# pci-e_x1-breakout.net
KiCad netlist of a schematic drawn in EAGLE
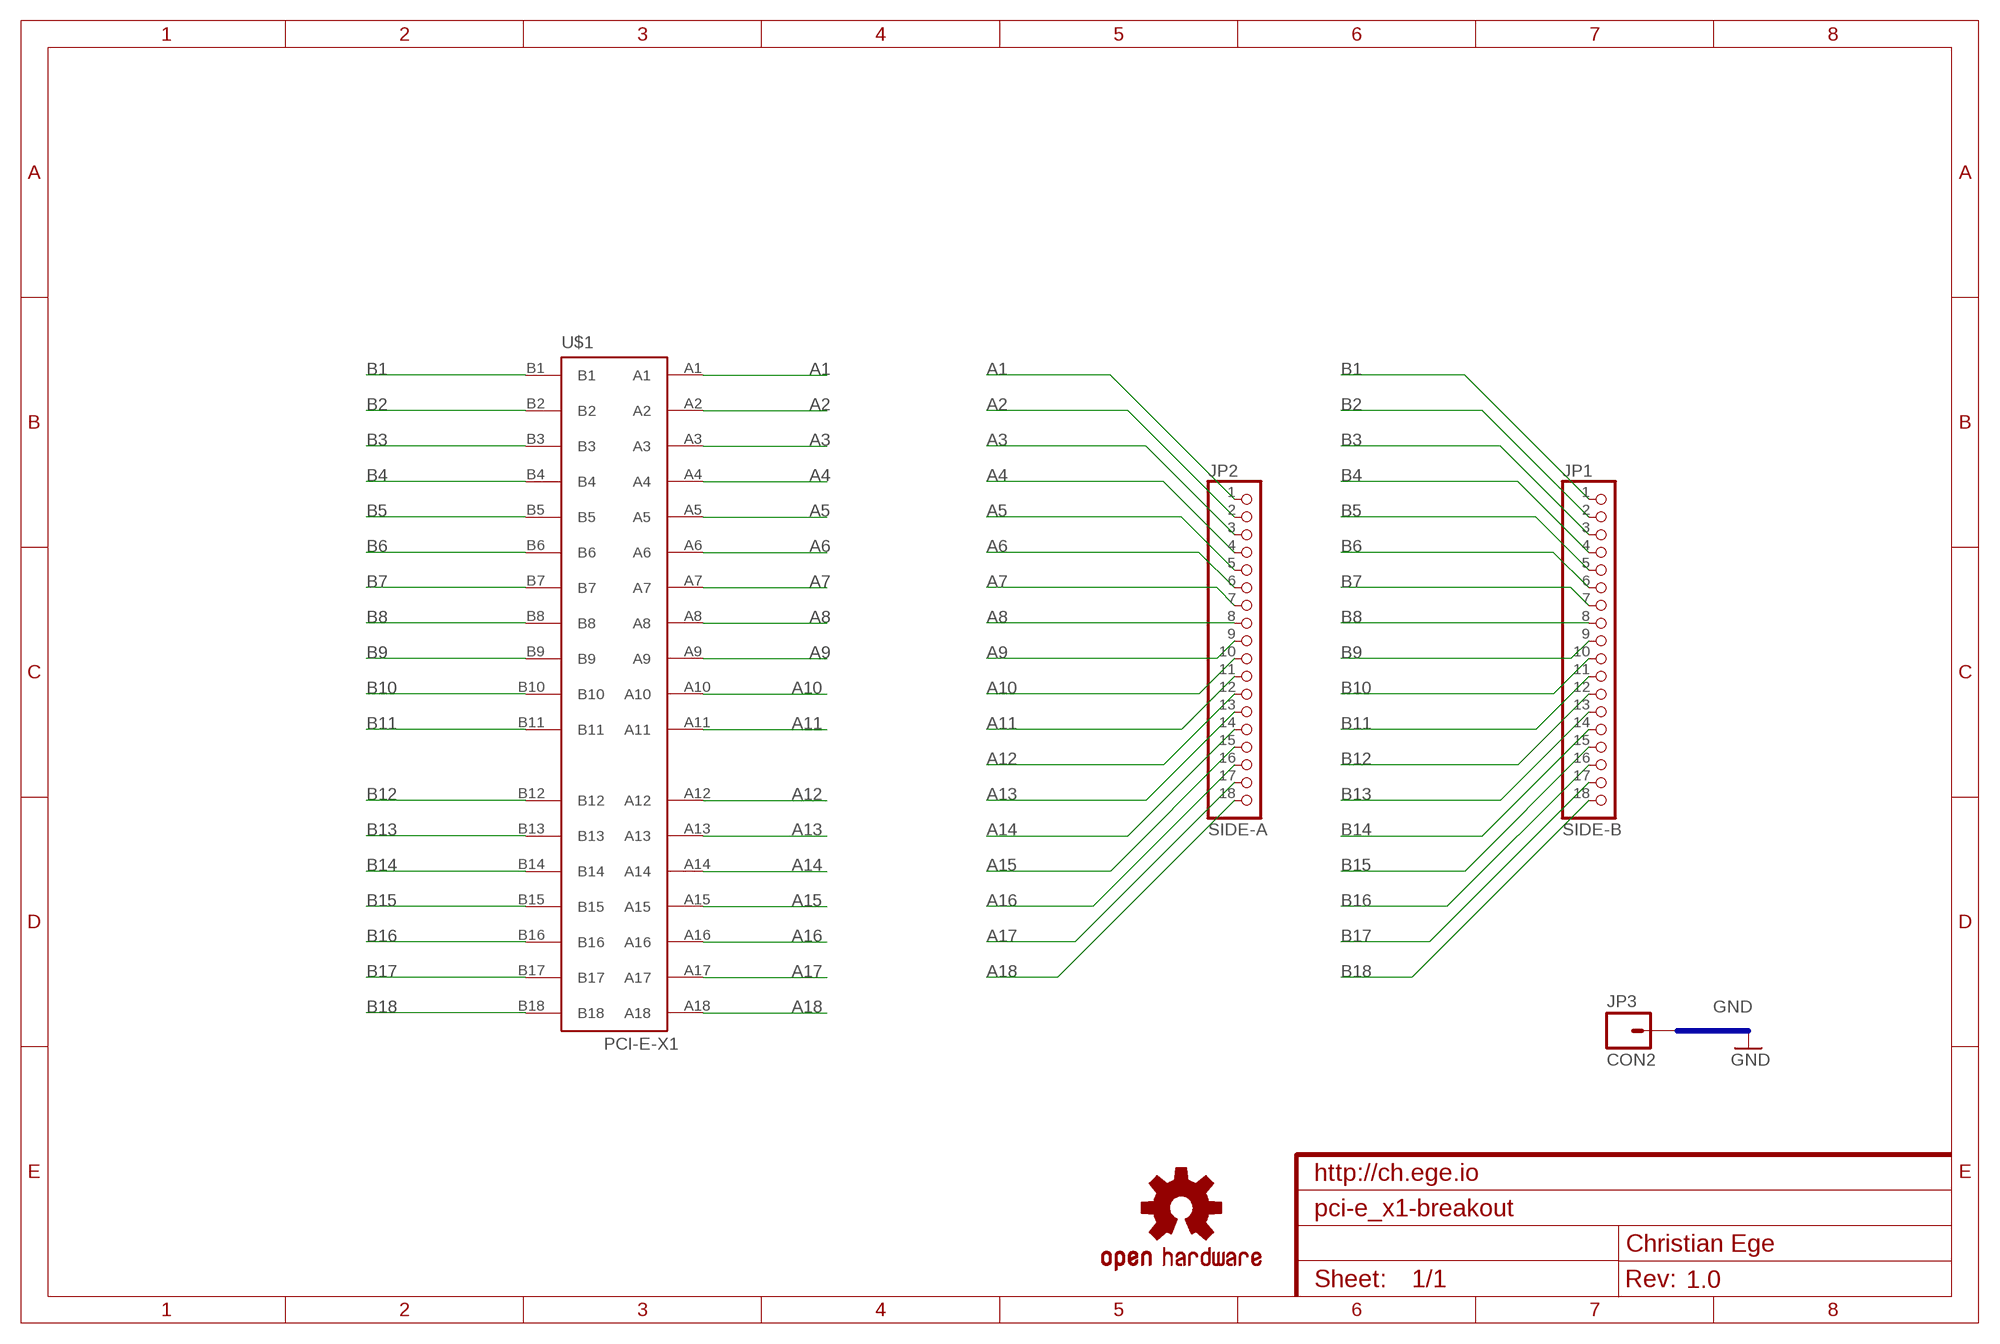
[diagram p0: schematic, sheet 1]

(export (version "E")
  (design (tool "Eeschema 10.0.6"))
  (components
    (comp (ref "JP1")
      (value "SIDE-B")
      (footprint "eagle-import:1X18")
      (libsource (lib "eagle-import") (part "PINHD-1X18"))
    )
    (comp (ref "JP2")
      (value "SIDE-A")
      (footprint "eagle-import:1X18")
      (libsource (lib "eagle-import") (part "PINHD-1X18"))
    )
    (comp (ref "JP3")
      (value "CON2")
      (footprint "eagle-import:1X01")
      (libsource (lib "eagle-import") (part "M01PTH"))
    )
    (comp (ref "LOGO1")
      (value "OSHW-LOGOS")
      (footprint "eagle-import:OSHW-LOGO-S")
      (libsource (lib "eagle-import") (part "OSHW-LOGOS"))
    )
    (comp (ref "U$1")
      (value "PCI-E-X1")
      (footprint "eagle-import:PCI-E-X1")
      (libsource (lib "eagle-import") (part "PCI-E-X1"))
    )
  )
  (nets
    (net (code "1") (name "/A1") (class "Default")
      (node (ref "JP2") (pin "1") (pinfunction "1_1") (pintype "passive"))
      (node (ref "U$1") (pin "A1") (pinfunction "A1_A1") (pintype "bidirectional"))
    )
    (net (code "2") (name "/A2") (class "Default")
      (node (ref "JP2") (pin "2") (pinfunction "2_2") (pintype "passive"))
      (node (ref "U$1") (pin "A2") (pinfunction "A2_A2") (pintype "bidirectional"))
    )
    (net (code "3") (name "/A3") (class "Default")
      (node (ref "JP2") (pin "3") (pinfunction "3_3") (pintype "passive"))
      (node (ref "U$1") (pin "A3") (pinfunction "A3_A3") (pintype "bidirectional"))
    )
    (net (code "4") (name "/A4") (class "Default")
      (node (ref "JP2") (pin "4") (pinfunction "4_4") (pintype "passive"))
      (node (ref "U$1") (pin "A4") (pinfunction "A4_A4") (pintype "bidirectional"))
    )
    (net (code "5") (name "/A5") (class "Default")
      (node (ref "JP2") (pin "5") (pinfunction "5_5") (pintype "passive"))
      (node (ref "U$1") (pin "A5") (pinfunction "A5_A5") (pintype "bidirectional"))
    )
    (net (code "6") (name "/A6") (class "Default")
      (node (ref "JP2") (pin "6") (pinfunction "6_6") (pintype "passive"))
      (node (ref "U$1") (pin "A6") (pinfunction "A6_A6") (pintype "bidirectional"))
    )
    (net (code "7") (name "/A7") (class "Default")
      (node (ref "JP2") (pin "7") (pinfunction "7_7") (pintype "passive"))
      (node (ref "U$1") (pin "A7") (pinfunction "A7_A7") (pintype "bidirectional"))
    )
    (net (code "8") (name "/A8") (class "Default")
      (node (ref "JP2") (pin "8") (pinfunction "8_8") (pintype "passive"))
      (node (ref "U$1") (pin "A8") (pinfunction "A8_A8") (pintype "bidirectional"))
    )
    (net (code "9") (name "/A9") (class "Default")
      (node (ref "JP2") (pin "9") (pinfunction "9_9") (pintype "passive"))
      (node (ref "U$1") (pin "A9") (pinfunction "A9_A9") (pintype "bidirectional"))
    )
    (net (code "10") (name "/A10") (class "Default")
      (node (ref "JP2") (pin "10") (pinfunction "10_10") (pintype "passive"))
      (node (ref "U$1") (pin "A10") (pinfunction "A10_A10") (pintype "bidirectional"))
    )
    (net (code "11") (name "/A11") (class "Default")
      (node (ref "JP2") (pin "11") (pinfunction "11_11") (pintype "passive"))
      (node (ref "U$1") (pin "A11") (pinfunction "A11_A11") (pintype "bidirectional"))
    )
    (net (code "12") (name "/A12") (class "Default")
      (node (ref "JP2") (pin "12") (pinfunction "12_12") (pintype "passive"))
      (node (ref "U$1") (pin "A12") (pinfunction "A12_A12") (pintype "bidirectional"))
    )
    (net (code "13") (name "/A13") (class "Default")
      (node (ref "JP2") (pin "13") (pinfunction "13_13") (pintype "passive"))
      (node (ref "U$1") (pin "A13") (pinfunction "A13_A13") (pintype "bidirectional"))
    )
    (net (code "14") (name "/A14") (class "Default")
      (node (ref "JP2") (pin "14") (pinfunction "14_14") (pintype "passive"))
      (node (ref "U$1") (pin "A14") (pinfunction "A14_A14") (pintype "bidirectional"))
    )
    (net (code "15") (name "/A15") (class "Default")
      (node (ref "JP2") (pin "15") (pinfunction "15_15") (pintype "passive"))
      (node (ref "U$1") (pin "A15") (pinfunction "A15_A15") (pintype "bidirectional"))
    )
    (net (code "16") (name "/A16") (class "Default")
      (node (ref "JP2") (pin "16") (pinfunction "16_16") (pintype "passive"))
      (node (ref "U$1") (pin "A16") (pinfunction "A16_A16") (pintype "bidirectional"))
    )
    (net (code "17") (name "/A17") (class "Default")
      (node (ref "JP2") (pin "17") (pinfunction "17_17") (pintype "passive"))
      (node (ref "U$1") (pin "A17") (pinfunction "A17_A17") (pintype "bidirectional"))
    )
    (net (code "18") (name "/A18") (class "Default")
      (node (ref "JP2") (pin "18") (pinfunction "18_18") (pintype "passive"))
      (node (ref "U$1") (pin "A18") (pinfunction "A18_A18") (pintype "bidirectional"))
    )
    (net (code "19") (name "/B1") (class "Default")
      (node (ref "JP1") (pin "1") (pinfunction "1_1") (pintype "passive"))
      (node (ref "U$1") (pin "B1") (pinfunction "B1_B1") (pintype "bidirectional"))
    )
    (net (code "20") (name "/B2") (class "Default")
      (node (ref "JP1") (pin "2") (pinfunction "2_2") (pintype "passive"))
      (node (ref "U$1") (pin "B2") (pinfunction "B2_B2") (pintype "bidirectional"))
    )
    (net (code "21") (name "/B3") (class "Default")
      (node (ref "JP1") (pin "3") (pinfunction "3_3") (pintype "passive"))
      (node (ref "U$1") (pin "B3") (pinfunction "B3_B3") (pintype "bidirectional"))
    )
    (net (code "22") (name "/B4") (class "Default")
      (node (ref "JP1") (pin "4") (pinfunction "4_4") (pintype "passive"))
      (node (ref "U$1") (pin "B4") (pinfunction "B4_B4") (pintype "bidirectional"))
    )
    (net (code "23") (name "/B5") (class "Default")
      (node (ref "JP1") (pin "5") (pinfunction "5_5") (pintype "passive"))
      (node (ref "U$1") (pin "B5") (pinfunction "B5_B5") (pintype "bidirectional"))
    )
    (net (code "24") (name "/B6") (class "Default")
      (node (ref "JP1") (pin "6") (pinfunction "6_6") (pintype "passive"))
      (node (ref "U$1") (pin "B6") (pinfunction "B6_B6") (pintype "bidirectional"))
    )
    (net (code "25") (name "/B7") (class "Default")
      (node (ref "JP1") (pin "7") (pinfunction "7_7") (pintype "passive"))
      (node (ref "U$1") (pin "B7") (pinfunction "B7_B7") (pintype "bidirectional"))
    )
    (net (code "26") (name "/B8") (class "Default")
      (node (ref "JP1") (pin "8") (pinfunction "8_8") (pintype "passive"))
      (node (ref "U$1") (pin "B8") (pinfunction "B8_B8") (pintype "bidirectional"))
    )
    (net (code "27") (name "/B9") (class "Default")
      (node (ref "JP1") (pin "9") (pinfunction "9_9") (pintype "passive"))
      (node (ref "U$1") (pin "B9") (pinfunction "B9_B9") (pintype "bidirectional"))
    )
    (net (code "28") (name "/B10") (class "Default")
      (node (ref "JP1") (pin "10") (pinfunction "10_10") (pintype "passive"))
      (node (ref "U$1") (pin "B10") (pinfunction "B10_B10") (pintype "bidirectional"))
    )
    (net (code "29") (name "/B11") (class "Default")
      (node (ref "JP1") (pin "11") (pinfunction "11_11") (pintype "passive"))
      (node (ref "U$1") (pin "B11") (pinfunction "B11_B11") (pintype "bidirectional"))
    )
    (net (code "30") (name "/B12") (class "Default")
      (node (ref "JP1") (pin "12") (pinfunction "12_12") (pintype "passive"))
      (node (ref "U$1") (pin "B12") (pinfunction "B12_B12") (pintype "bidirectional"))
    )
    (net (code "31") (name "/B13") (class "Default")
      (node (ref "JP1") (pin "13") (pinfunction "13_13") (pintype "passive"))
      (node (ref "U$1") (pin "B13") (pinfunction "B13_B13") (pintype "bidirectional"))
    )
    (net (code "32") (name "/B14") (class "Default")
      (node (ref "JP1") (pin "14") (pinfunction "14_14") (pintype "passive"))
      (node (ref "U$1") (pin "B14") (pinfunction "B14_B14") (pintype "bidirectional"))
    )
    (net (code "33") (name "/B15") (class "Default")
      (node (ref "JP1") (pin "15") (pinfunction "15_15") (pintype "passive"))
      (node (ref "U$1") (pin "B15") (pinfunction "B15_B15") (pintype "bidirectional"))
    )
    (net (code "34") (name "/B16") (class "Default")
      (node (ref "JP1") (pin "16") (pinfunction "16_16") (pintype "passive"))
      (node (ref "U$1") (pin "B16") (pinfunction "B16_B16") (pintype "bidirectional"))
    )
    (net (code "35") (name "/B17") (class "Default")
      (node (ref "JP1") (pin "17") (pinfunction "17_17") (pintype "passive"))
      (node (ref "U$1") (pin "B17") (pinfunction "B17_B17") (pintype "bidirectional"))
    )
    (net (code "36") (name "/B18") (class "Default")
      (node (ref "JP1") (pin "18") (pinfunction "18_18") (pintype "passive"))
      (node (ref "U$1") (pin "B18") (pinfunction "B18_B18") (pintype "bidirectional"))
    )
    (net (code "37") (name "GND") (class "Default")
      (node (ref "JP3") (pin "1") (pinfunction "1_1") (pintype "passive"))
    )
  )
)
